# SEED.net
KiCad netlist of a schematic drawn in EAGLE
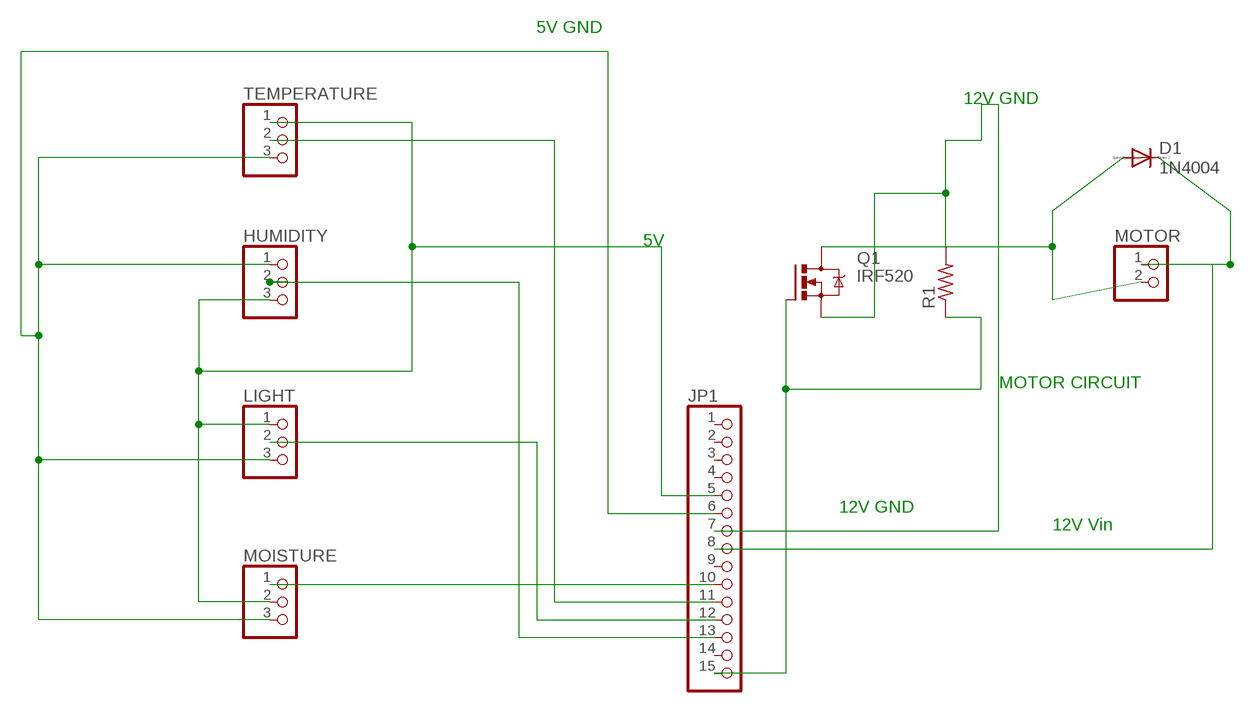
[diagram p0: schematic, sheet 1]

(export (version "E")
  (design (tool "Eeschema 10.0.6"))
  (components
    (comp (ref "D1")
      (value "1N4004")
      (footprint "eagle-import:DO41-10")
      (libsource (lib "eagle-import") (part "1N4004"))
    )
    (comp (ref "HUMIDITY")
      (value "PINHD-1X3")
      (footprint "eagle-import:1X03")
      (libsource (lib "eagle-import") (part "PINHD-1X3"))
    )
    (comp (ref "JP1")
      (value "PINHD-1X15")
      (footprint "eagle-import:1X15")
      (libsource (lib "eagle-import") (part "PINHD-1X15"))
    )
    (comp (ref "LIGHT")
      (value "PINHD-1X3")
      (footprint "eagle-import:1X03")
      (libsource (lib "eagle-import") (part "PINHD-1X3"))
    )
    (comp (ref "MOISTURE")
      (value "PINHD-1X3")
      (footprint "eagle-import:1X03")
      (libsource (lib "eagle-import") (part "PINHD-1X3"))
    )
    (comp (ref "MOTOR")
      (value "PINHD-1X2")
      (footprint "eagle-import:1X02")
      (libsource (lib "eagle-import") (part "PINHD-1X2"))
    )
    (comp (ref "Q1")
      (value "IRF520")
      (footprint "eagle-import:TO220BV")
      (libsource (lib "eagle-import") (part "IRF520"))
    )
    (comp (ref "R1")
      (value "R-US_0207/12")
      (footprint "eagle-import:0207_12")
      (libsource (lib "eagle-import") (part "R-US_0207/12"))
    )
    (comp (ref "TEMPERATURE")
      (value "PINHD-1X3")
      (footprint "eagle-import:1X03")
      (libsource (lib "eagle-import") (part "PINHD-1X3"))
    )
  )
  (nets
    (net (code "1") (name "Net-(D1-PadA)") (class "Default")
      (node (ref "D1") (pin "A") (pinfunction "A_A") (pintype "passive"))
      (node (ref "MOTOR") (pin "2") (pinfunction "2_2") (pintype "passive"))
      (node (ref "Q1") (pin "D") (pinfunction "D_D") (pintype "passive"))
    )
    (net (code "2") (name "Net-(D1-PadC)") (class "Default")
      (node (ref "D1") (pin "C") (pinfunction "C_C") (pintype "passive"))
      (node (ref "JP1") (pin "8") (pinfunction "8_8") (pintype "passive"))
      (node (ref "MOTOR") (pin "1") (pinfunction "1_1") (pintype "passive"))
    )
    (net (code "3") (name "Net-(HUMIDITY-Pad1)") (class "Default")
      (node (ref "HUMIDITY") (pin "1") (pinfunction "1_1") (pintype "passive"))
      (node (ref "JP1") (pin "6") (pinfunction "6_6") (pintype "passive"))
      (node (ref "LIGHT") (pin "3") (pinfunction "3_3") (pintype "passive"))
      (node (ref "MOISTURE") (pin "3") (pinfunction "3_3") (pintype "passive"))
      (node (ref "TEMPERATURE") (pin "3") (pinfunction "3_3") (pintype "passive"))
    )
    (net (code "4") (name "Net-(HUMIDITY-Pad2)") (class "Default")
      (node (ref "HUMIDITY") (pin "2") (pinfunction "2_2") (pintype "passive"))
      (node (ref "JP1") (pin "13") (pinfunction "13_13") (pintype "passive"))
    )
    (net (code "5") (name "Net-(HUMIDITY-Pad3)") (class "Default")
      (node (ref "HUMIDITY") (pin "3") (pinfunction "3_3") (pintype "passive"))
      (node (ref "JP1") (pin "5") (pinfunction "5_5") (pintype "passive"))
      (node (ref "LIGHT") (pin "1") (pinfunction "1_1") (pintype "passive"))
      (node (ref "MOISTURE") (pin "2") (pinfunction "2_2") (pintype "passive"))
      (node (ref "TEMPERATURE") (pin "1") (pinfunction "1_1") (pintype "passive"))
    )
    (net (code "6") (name "Net-(JP1-Pad7)") (class "Default")
      (node (ref "JP1") (pin "7") (pinfunction "7_7") (pintype "passive"))
      (node (ref "Q1") (pin "S") (pinfunction "S_S") (pintype "passive"))
      (node (ref "R1") (pin "2") (pinfunction "2_2") (pintype "passive"))
    )
    (net (code "7") (name "Net-(JP1-Pad10)") (class "Default")
      (node (ref "JP1") (pin "10") (pinfunction "10_10") (pintype "passive"))
      (node (ref "MOISTURE") (pin "1") (pinfunction "1_1") (pintype "passive"))
    )
    (net (code "8") (name "Net-(JP1-Pad11)") (class "Default")
      (node (ref "JP1") (pin "11") (pinfunction "11_11") (pintype "passive"))
      (node (ref "TEMPERATURE") (pin "2") (pinfunction "2_2") (pintype "passive"))
    )
    (net (code "9") (name "Net-(JP1-Pad12)") (class "Default")
      (node (ref "JP1") (pin "12") (pinfunction "12_12") (pintype "passive"))
      (node (ref "LIGHT") (pin "2") (pinfunction "2_2") (pintype "passive"))
    )
    (net (code "10") (name "Net-(JP1-Pad15)") (class "Default")
      (node (ref "JP1") (pin "15") (pinfunction "15_15") (pintype "passive"))
      (node (ref "Q1") (pin "G") (pinfunction "G_G") (pintype "passive"))
      (node (ref "R1") (pin "1") (pinfunction "1_1") (pintype "passive"))
    )
    (net (code "11") (name "unconnected-(JP1-Pad1)") (class "Default")
      (node (ref "JP1") (pin "1") (pinfunction "1_1") (pintype "passive"))
    )
    (net (code "12") (name "unconnected-(JP1-Pad2)") (class "Default")
      (node (ref "JP1") (pin "2") (pinfunction "2_2") (pintype "passive"))
    )
    (net (code "13") (name "unconnected-(JP1-Pad3)") (class "Default")
      (node (ref "JP1") (pin "3") (pinfunction "3_3") (pintype "passive"))
    )
    (net (code "14") (name "unconnected-(JP1-Pad4)") (class "Default")
      (node (ref "JP1") (pin "4") (pinfunction "4_4") (pintype "passive"))
    )
    (net (code "15") (name "unconnected-(JP1-Pad9)") (class "Default")
      (node (ref "JP1") (pin "9") (pinfunction "9_9") (pintype "passive"))
    )
    (net (code "16") (name "unconnected-(JP1-Pad14)") (class "Default")
      (node (ref "JP1") (pin "14") (pinfunction "14_14") (pintype "passive"))
    )
  )
)
